# CAN_3V3.net
KiCad netlist of a schematic drawn in Altium Designer
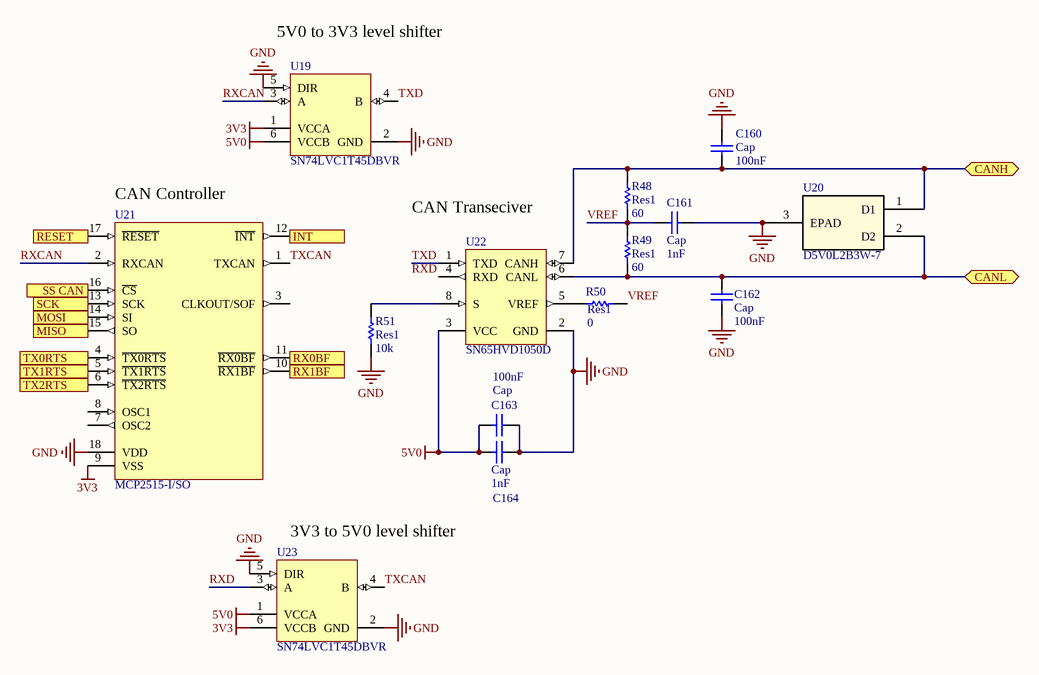
[diagram p0: CAN 3V3.SchDoc]

(export (version "E")
  (design (tool "Eeschema 10.0.6"))
  (components
    (comp (ref "C160")
      (value "Cap")
      (footprint "1608[0603]")
      (description "Capacitor")
      (fields (field (name "ALTIUM_VALUE") "100nF") (field (name "PUBLISHER") "Altium Limited"))
      (libsource (lib "Miscellaneous Devices") (part "Cap"))
    )
    (comp (ref "C161")
      (value "Cap")
      (footprint "1608[0603]")
      (description "Capacitor")
      (fields (field (name "ALTIUM_VALUE") "1nF") (field (name "PUBLISHER") "Altium Limited"))
      (libsource (lib "Miscellaneous Devices") (part "Cap"))
    )
    (comp (ref "C162")
      (value "Cap")
      (footprint "1608[0603]")
      (description "Capacitor")
      (fields (field (name "ALTIUM_VALUE") "100nF") (field (name "PUBLISHER") "Altium Limited"))
      (libsource (lib "Miscellaneous Devices") (part "Cap"))
    )
    (comp (ref "C163")
      (value "Cap")
      (footprint "1608[0603]")
      (description "Capacitor")
      (fields (field (name "ALTIUM_VALUE") "100nF") (field (name "PUBLISHER") "Altium Limited"))
      (libsource (lib "Miscellaneous Devices") (part "Cap"))
    )
    (comp (ref "C164")
      (value "Cap")
      (footprint "1608[0603]")
      (description "Capacitor")
      (fields (field (name "ALTIUM_VALUE") "1nF") (field (name "PUBLISHER") "Altium Limited"))
      (libsource (lib "Miscellaneous Devices") (part "Cap"))
    )
    (comp (ref "R48")
      (value "Res1")
      (footprint "1608[0603]")
      (description "Resistor")
      (fields (field (name "ALTIUM_VALUE") "60") (field (name "PUBLISHER") "Altium Limited"))
      (libsource (lib "Miscellaneous Devices") (part "Res1"))
    )
    (comp (ref "R49")
      (value "Res1")
      (footprint "1608[0603]")
      (description "Resistor")
      (fields (field (name "ALTIUM_VALUE") "60") (field (name "PUBLISHER") "Altium Limited"))
      (libsource (lib "Miscellaneous Devices") (part "Res1"))
    )
    (comp (ref "R50")
      (value "Res1")
      (footprint "1608[0603]")
      (description "Resistor")
      (fields (field (name "ALTIUM_VALUE") "0") (field (name "PUBLISHER") "Altium Limited"))
      (libsource (lib "Miscellaneous Devices") (part "Res1"))
    )
    (comp (ref "R51")
      (value "Res1")
      (footprint "1608[0603]")
      (description "Resistor")
      (fields (field (name "ALTIUM_VALUE") "10k") (field (name "PUBLISHER") "Altium Limited"))
      (libsource (lib "Miscellaneous Devices") (part "Res1"))
    )
    (comp (ref "U19")
      (value "SN74LVC1T45DBVR")
      (footprint "DBV0006A_L")
      (fields
        (field (name "MANUFACTURER") "Texas Instruments")
        (field (name "GENERIC PART NUMBER") "SN74LVC1T45")
      )
      (libsource (lib "Altium Content Vault") (part "TI-SN74XVC1T45-6"))
    )
    (comp (ref "U20")
      (value "D5V0L2B3W-7")
      (footprint "SOT-323_DIO")
      (description "No Description Available")
      (fields (field (name "COPYRIGHT") "Copyright (C) 2018 Accelerated Designs. All rights reserved"))
      (libsource (lib "D5V0L2B3W-7 library") (part "D5V0L2B3W-7"))
    )
    (comp (ref "U21")
      (value "MCP2515-I/SO")
      (footprint "SOIC-SO18_L")
      (description "Stand-Alone CAN Controller With SPI Interface, 18-Pin SOIC, Industrial Temperature")
      (libsource (lib "Altium Content Vault") (part "COM-CAN-MCP2515-18"))
    )
    (comp (ref "U22")
      (value "SN65HVD1050D")
      (footprint "D0008A_N")
      (fields (field (name "MANUFACTURER") "Texas Instruments"))
      (libsource (lib "Altium Content Vault") (part "TI-SN65HVD1050-SOIC_D-8"))
    )
    (comp (ref "U23")
      (value "SN74LVC1T45DBVR")
      (footprint "DBV0006A_L")
      (fields
        (field (name "MANUFACTURER") "Texas Instruments")
        (field (name "GENERIC PART NUMBER") "SN74LVC1T45")
      )
      (libsource (lib "Altium Content Vault") (part "TI-SN74XVC1T45-6"))
    )
  )
  (nets
    (net (code "1") (name "/CANH") (class "Default")
      (node (ref "C160") (pin "2") (pinfunction "2_2") (pintype "passive"))
      (node (ref "R48") (pin "1") (pinfunction "1_1") (pintype "passive"))
      (node (ref "U20") (pin "1") (pinfunction "D1_1") (pintype "passive"))
      (node (ref "U22") (pin "7") (pinfunction "CANH_7") (pintype "bidirectional"))
    )
    (net (code "2") (name "/CANL") (class "Default")
      (node (ref "C162") (pin "2") (pinfunction "2_2") (pintype "passive"))
      (node (ref "R49") (pin "1") (pinfunction "1_1") (pintype "passive"))
      (node (ref "U20") (pin "2") (pinfunction "D2_2") (pintype "passive"))
      (node (ref "U22") (pin "6") (pinfunction "CANL_6") (pintype "bidirectional"))
    )
    (net (code "3") (name "/INT") (class "Default")
      (node (ref "U21") (pin "12") (pinfunction "~{INT}_12") (pintype "output"))
    )
    (net (code "4") (name "/MISO") (class "Default")
      (node (ref "U21") (pin "15") (pinfunction "SO_15") (pintype "output"))
    )
    (net (code "5") (name "/MOSI") (class "Default")
      (node (ref "U21") (pin "14") (pinfunction "SI_14") (pintype "input"))
    )
    (net (code "6") (name "/RESET") (class "Default")
      (node (ref "U21") (pin "17") (pinfunction "~{RESET}_17") (pintype "input"))
    )
    (net (code "7") (name "/RX0BF") (class "Default")
      (node (ref "U21") (pin "11") (pinfunction "~{RX0BF}_11") (pintype "output"))
    )
    (net (code "8") (name "/RX1BF") (class "Default")
      (node (ref "U21") (pin "10") (pinfunction "~{RX1BF}_10") (pintype "output"))
    )
    (net (code "9") (name "/RXCAN") (class "Default")
      (node (ref "U19") (pin "3") (pinfunction "A_3") (pintype "bidirectional"))
      (node (ref "U21") (pin "2") (pinfunction "RXCAN_2") (pintype "input"))
    )
    (net (code "10") (name "/RXD") (class "Default")
      (node (ref "U23") (pin "3") (pinfunction "A_3") (pintype "bidirectional"))
    )
    (net (code "11") (name "/SCK") (class "Default")
      (node (ref "U21") (pin "13") (pinfunction "SCK_13") (pintype "input"))
    )
    (net (code "12") (name "/SS CAN") (class "Default")
      (node (ref "U21") (pin "16") (pinfunction "~{CS}_16") (pintype "input"))
    )
    (net (code "13") (name "/TX0RTS") (class "Default")
      (node (ref "U21") (pin "4") (pinfunction "~{TX0RTS}_4") (pintype "input"))
    )
    (net (code "14") (name "/TX1RTS") (class "Default")
      (node (ref "U21") (pin "5") (pinfunction "~{TX1RTS}_5") (pintype "input"))
    )
    (net (code "15") (name "/TX2RTS") (class "Default")
      (node (ref "U21") (pin "6") (pinfunction "~{TX2RTS}_6") (pintype "input"))
    )
    (net (code "16") (name "/TXCAN") (class "Default")
      (node (ref "U21") (pin "1") (pinfunction "TXCAN_1") (pintype "output"))
      (node (ref "U23") (pin "4") (pinfunction "B_4") (pintype "bidirectional"))
    )
    (net (code "17") (name "/TXD") (class "Default")
      (node (ref "U19") (pin "4") (pinfunction "B_4") (pintype "bidirectional"))
      (node (ref "U22") (pin "1") (pinfunction "TXD_1") (pintype "input"))
    )
    (net (code "18") (name "/VREF") (class "Default")
      (node (ref "C161") (pin "1") (pinfunction "1_1") (pintype "passive"))
      (node (ref "R48") (pin "2") (pinfunction "2_2") (pintype "passive"))
      (node (ref "R49") (pin "2") (pinfunction "2_2") (pintype "passive"))
      (node (ref "R50") (pin "2") (pinfunction "2_2") (pintype "passive"))
    )
    (net (code "19") (name "3V3") (class "Default")
      (node (ref "U19") (pin "1") (pinfunction "VCCA_1") (pintype "power_in"))
      (node (ref "U21") (pin "9") (pinfunction "VSS_9") (pintype "power_in"))
      (node (ref "U23") (pin "6") (pinfunction "VCCB_6") (pintype "power_in"))
    )
    (net (code "20") (name "5V0") (class "Default")
      (node (ref "C163") (pin "1") (pinfunction "1_1") (pintype "passive"))
      (node (ref "C164") (pin "2") (pinfunction "2_2") (pintype "passive"))
      (node (ref "U19") (pin "6") (pinfunction "VCCB_6") (pintype "power_in"))
      (node (ref "U22") (pin "3") (pinfunction "VCC_3") (pintype "power_in"))
      (node (ref "U23") (pin "1") (pinfunction "VCCA_1") (pintype "power_in"))
    )
    (net (code "21") (name "GND") (class "Default")
      (node (ref "C160") (pin "1") (pinfunction "1_1") (pintype "passive"))
      (node (ref "C161") (pin "2") (pinfunction "2_2") (pintype "passive"))
      (node (ref "C162") (pin "1") (pinfunction "1_1") (pintype "passive"))
      (node (ref "C163") (pin "2") (pinfunction "2_2") (pintype "passive"))
      (node (ref "C164") (pin "1") (pinfunction "1_1") (pintype "passive"))
      (node (ref "R51") (pin "1") (pinfunction "1_1") (pintype "passive"))
      (node (ref "U19") (pin "2") (pinfunction "GND_2") (pintype "power_in"))
      (node (ref "U19") (pin "5") (pinfunction "DIR_5") (pintype "input"))
      (node (ref "U20") (pin "3") (pinfunction "EPAD_3") (pintype "passive"))
      (node (ref "U21") (pin "18") (pinfunction "VDD_18") (pintype "power_in"))
      (node (ref "U22") (pin "2") (pinfunction "GND_2") (pintype "power_in"))
      (node (ref "U23") (pin "2") (pinfunction "GND_2") (pintype "power_in"))
      (node (ref "U23") (pin "5") (pinfunction "DIR_5") (pintype "input"))
    )
    (net (code "22") (name "Net-(U22-S)") (class "Default")
      (node (ref "R51") (pin "2") (pinfunction "2_2") (pintype "passive"))
      (node (ref "U22") (pin "8") (pinfunction "S_8") (pintype "input"))
    )
    (net (code "23") (name "Net-(U22-VREF)") (class "Default")
      (node (ref "R50") (pin "1") (pinfunction "1_1") (pintype "passive"))
      (node (ref "U22") (pin "5") (pinfunction "VREF_5") (pintype "output"))
    )
    (net (code "24") (name "unconnected-(U21-CLKOUT{slash}SOF-Pad3)") (class "Default")
      (node (ref "U21") (pin "3") (pinfunction "CLKOUT/SOF_3") (pintype "output"))
    )
    (net (code "25") (name "unconnected-(U21-OSC1-Pad8)") (class "Default")
      (node (ref "U21") (pin "8") (pinfunction "OSC1_8") (pintype "input"))
    )
    (net (code "26") (name "unconnected-(U21-OSC2-Pad7)") (class "Default")
      (node (ref "U21") (pin "7") (pinfunction "OSC2_7") (pintype "output"))
    )
    (net (code "27") (name "unconnected-(U22-RXD-Pad4)") (class "Default")
      (node (ref "U22") (pin "4") (pinfunction "RXD_4") (pintype "output"))
    )
  )
)
